# output.net
KiCad netlist of a schematic drawn in Altium Designer
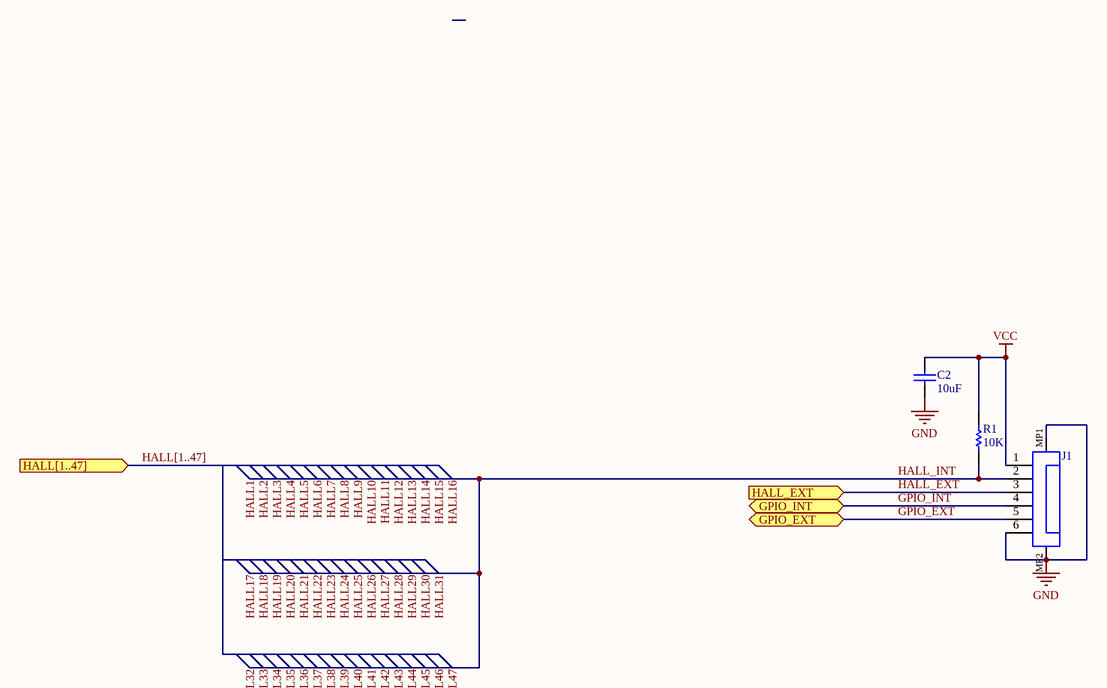
[diagram p0: output.SchDoc]

(export (version "E")
  (design (tool "Eeschema 10.0.6"))
  (components
    (comp (ref "C2")
      (value "10uF")
      (footprint "CAPC2013X140X50LL20T25")
      (fields (field (name "PART NUMBER") "C0805C106K8PACTU") (field (name "MANUFACTURER") "Kemet"))
      (libsource (lib "Altium Content Vault") (part "CAP"))
    )
    (comp (ref "J1")
      (value "68610614422")
      (footprint "68610614422")
      (description "SMT ZIF Connectors WR-FPC, Horizontal, Bottom Contact, pitch 1 mm, 6 pins")
      (fields (field (name "MANUFACTURER") "Wurth Elektronik") (field (name "PUBLISHER") "WurthElektronik"))
      (libsource (lib "Altium Content Vault") (part "WE-68X1061XXX22-6"))
    )
    (comp (ref "R1")
      (value "10K")
      (footprint "RESC1608X55X30LL15T15")
      (fields (field (name "PART NUMBER") "ERJ-3EKF1002V") (field (name "MANUFACTURER") "Panasonic"))
      (libsource (lib "Altium Content Vault") (part "RES"))
    )
  )
  (nets
    (net (code "1") (name "/GPIO_EXT") (class "Default")
      (node (ref "J1") (pin "5") (pinfunction "5_5") (pintype "passive"))
    )
    (net (code "2") (name "/GPIO_INT") (class "Default")
      (node (ref "J1") (pin "4") (pinfunction "4_4") (pintype "passive"))
    )
    (net (code "3") (name "/HALL9") (class "Default")
      (node (ref "J1") (pin "2") (pinfunction "2_2") (pintype "passive"))
      (node (ref "R1") (pin "1") (pinfunction "1_1") (pintype "passive"))
    )
    (net (code "5") (name "/HALL_EXT") (class "Default")
      (node (ref "J1") (pin "3") (pinfunction "3_3") (pintype "passive"))
    )
    (net (code "6") (name "GND") (class "Default")
      (node (ref "C2") (pin "1") (pinfunction "1_1") (pintype "passive"))
      (node (ref "J1") (pin "6") (pinfunction "6_6") (pintype "passive"))
      (node (ref "J1") (pin "MP1") (pinfunction "MP1_MP1") (pintype "passive"))
      (node (ref "J1") (pin "MP2") (pinfunction "MP2_MP2") (pintype "passive"))
    )
    (net (code "7") (name "VCC") (class "Default")
      (node (ref "C2") (pin "2") (pinfunction "2_2") (pintype "passive"))
      (node (ref "J1") (pin "1") (pinfunction "1_1") (pintype "passive"))
      (node (ref "R1") (pin "2") (pinfunction "2_2") (pintype "passive"))
    )
  )
)
